# vera-module.net
KiCad netlist of a schematic drawn in EAGLE
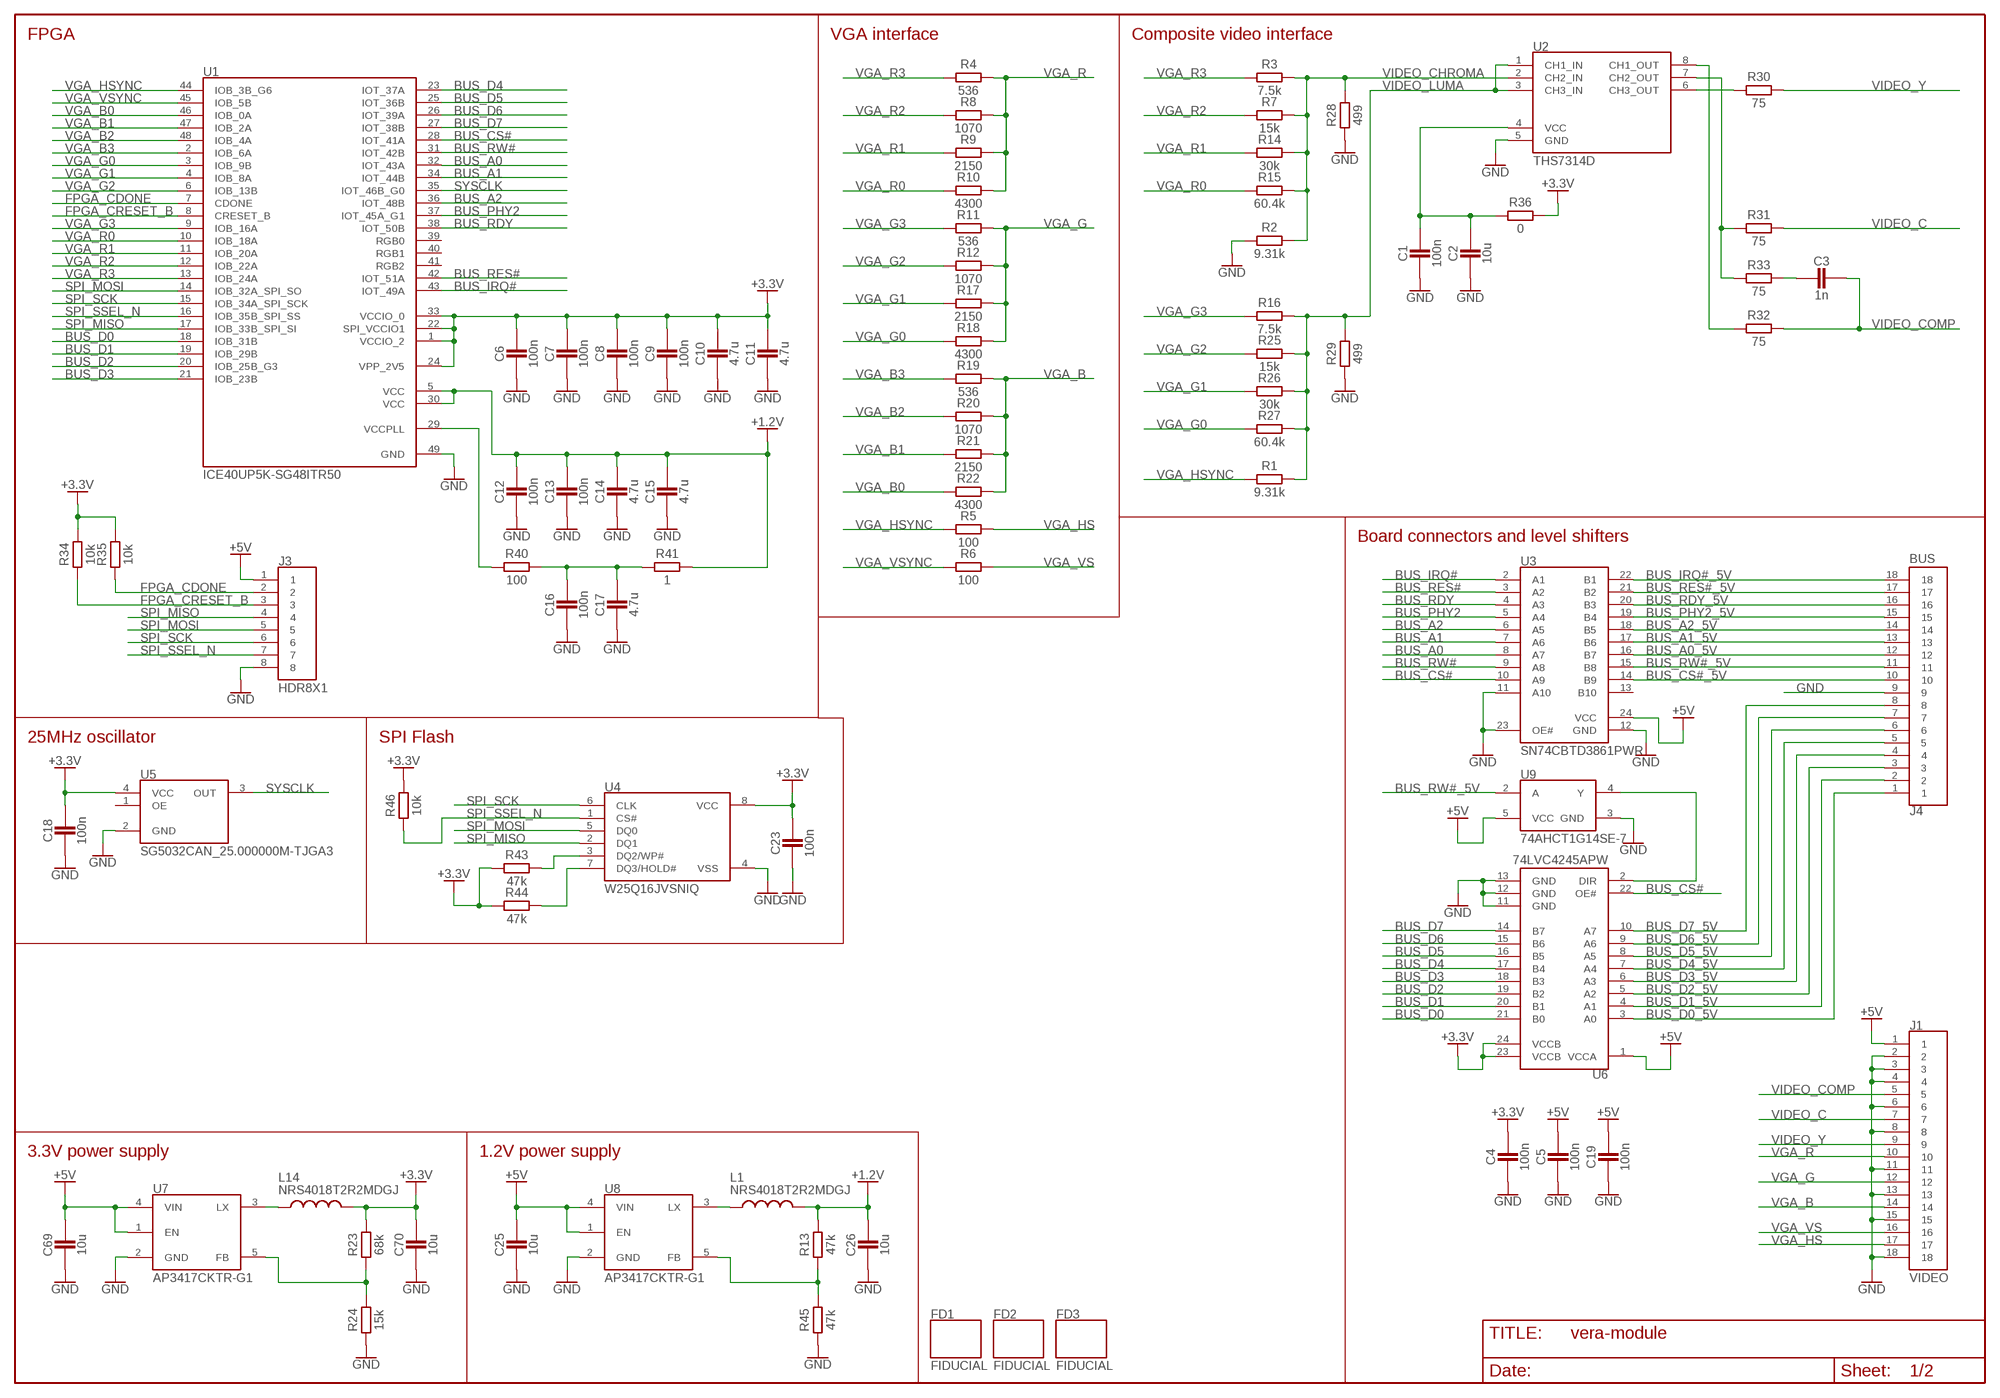
[diagram p0: schematic, sheet 1]
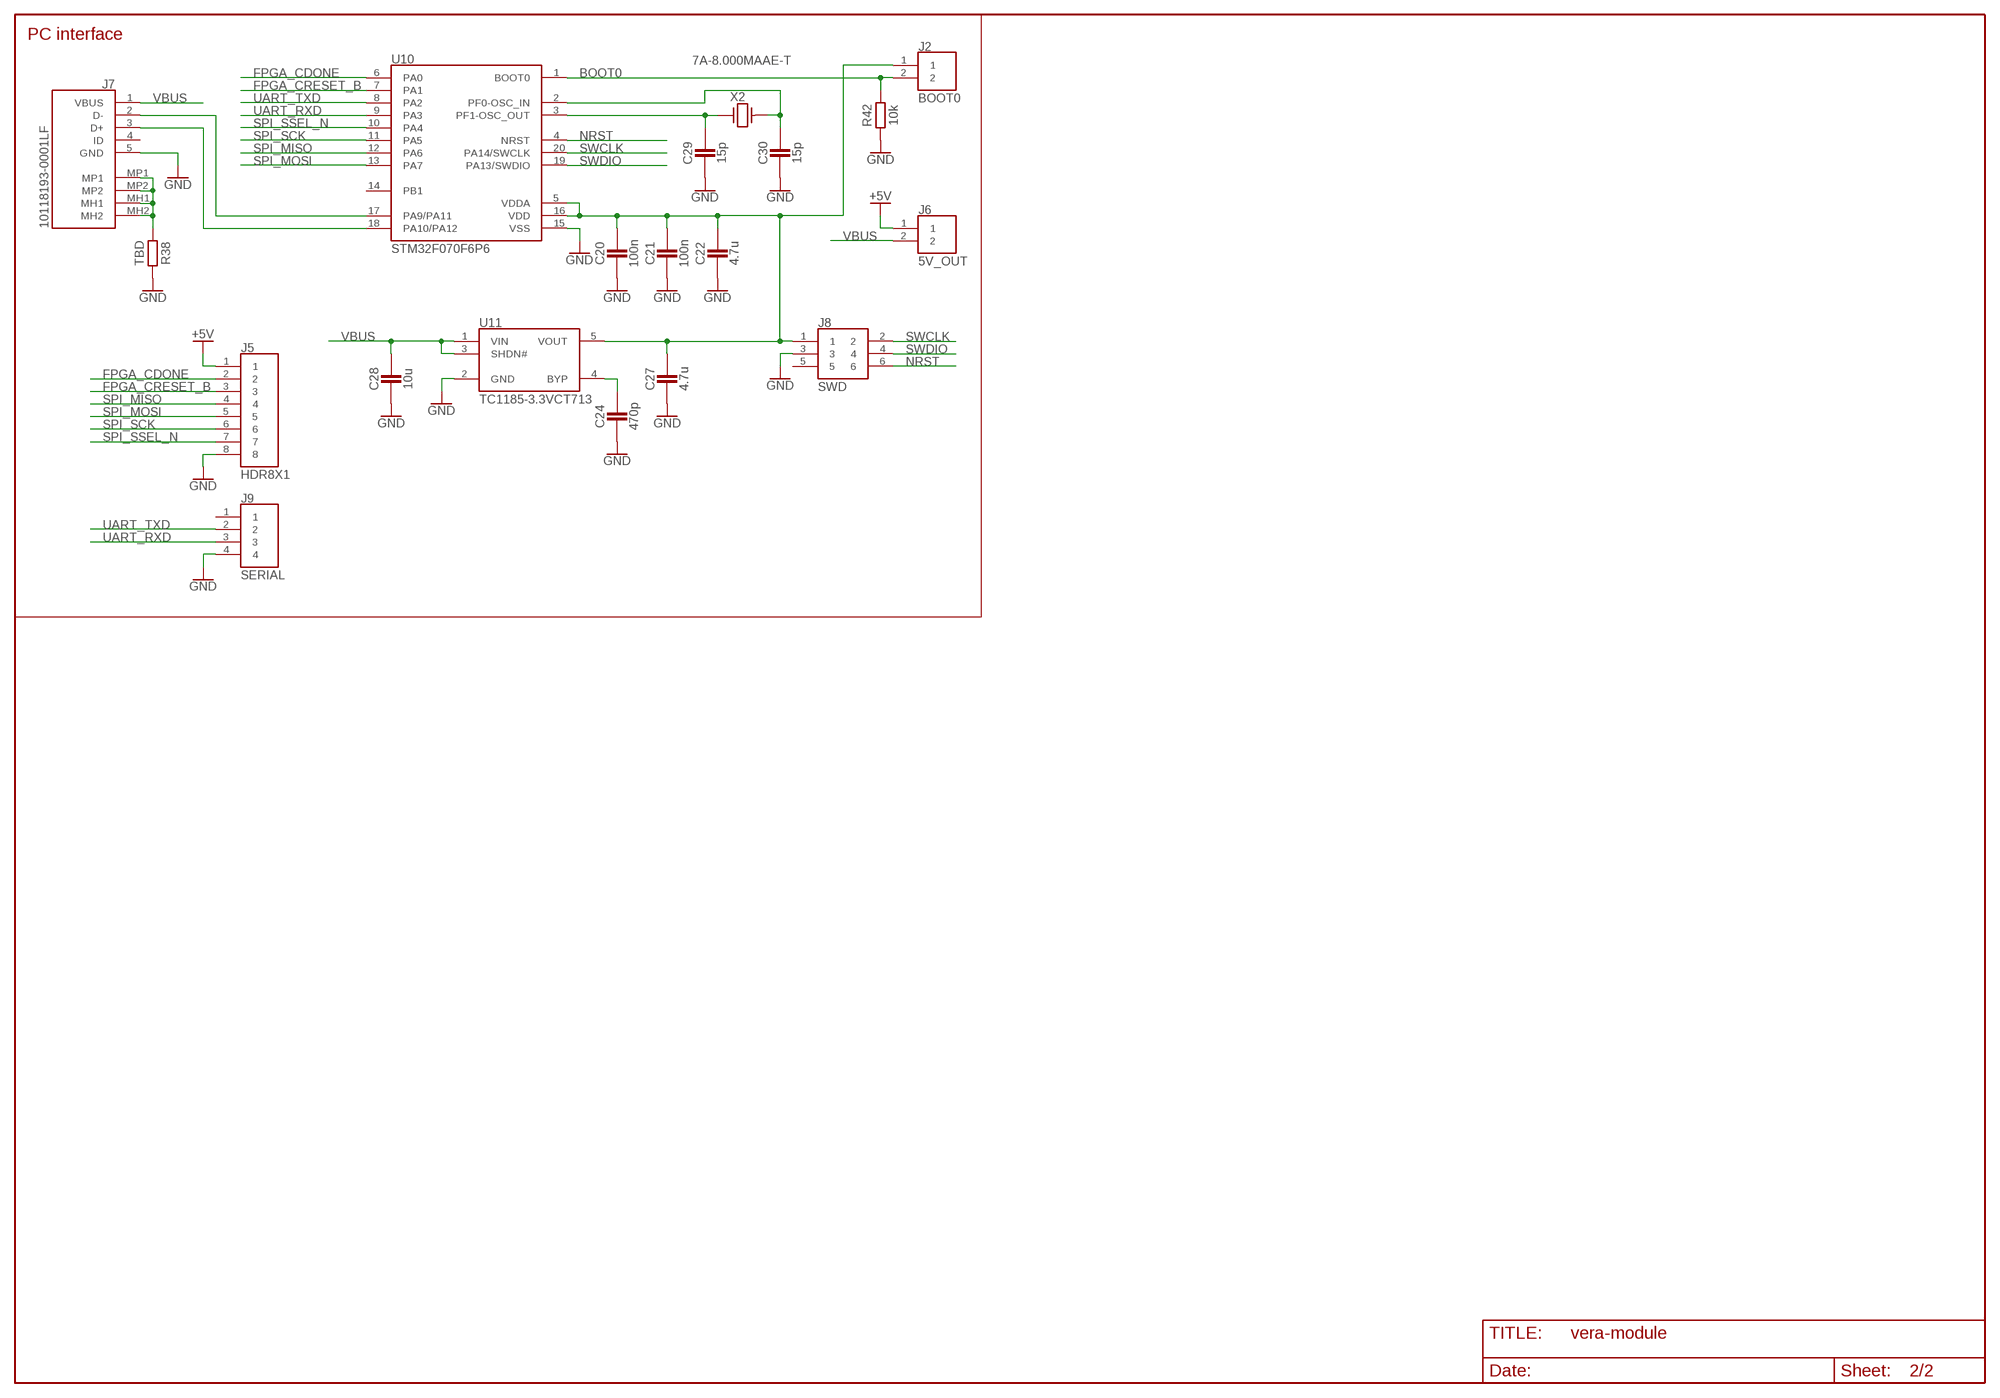
[diagram p1: schematic, sheet 2]

(export (version "E")
  (design (tool "Eeschema 10.0.6"))
  (components
    (comp (ref "C1")
      (value "100n")
      (footprint "eagle-import:C0603")
      (libsource (lib "eagle-import") (part "CAPACITOR0603"))
    )
    (comp (ref "C2")
      (value "10u")
      (footprint "eagle-import:C0805")
      (libsource (lib "eagle-import") (part "CAPACITOR0805"))
    )
    (comp (ref "C3")
      (value "1n")
      (footprint "eagle-import:C0603")
      (libsource (lib "eagle-import") (part "CAPACITOR0603"))
    )
    (comp (ref "C4")
      (value "100n")
      (footprint "eagle-import:C0603")
      (libsource (lib "eagle-import") (part "CAPACITOR0603"))
    )
    (comp (ref "C5")
      (value "100n")
      (footprint "eagle-import:C0603")
      (libsource (lib "eagle-import") (part "CAPACITOR0603"))
    )
    (comp (ref "C6")
      (value "100n")
      (footprint "eagle-import:C0603")
      (libsource (lib "eagle-import") (part "CAPACITOR0603"))
    )
    (comp (ref "C7")
      (value "100n")
      (footprint "eagle-import:C0603")
      (libsource (lib "eagle-import") (part "CAPACITOR0603"))
    )
    (comp (ref "C8")
      (value "100n")
      (footprint "eagle-import:C0603")
      (libsource (lib "eagle-import") (part "CAPACITOR0603"))
    )
    (comp (ref "C9")
      (value "100n")
      (footprint "eagle-import:C0603")
      (libsource (lib "eagle-import") (part "CAPACITOR0603"))
    )
    (comp (ref "C10")
      (value "4.7u")
      (footprint "eagle-import:C0603")
      (libsource (lib "eagle-import") (part "CAPACITOR0603"))
    )
    (comp (ref "C11")
      (value "4.7u")
      (footprint "eagle-import:C0603")
      (libsource (lib "eagle-import") (part "CAPACITOR0603"))
    )
    (comp (ref "C12")
      (value "100n")
      (footprint "eagle-import:C0603")
      (libsource (lib "eagle-import") (part "CAPACITOR0603"))
    )
    (comp (ref "C13")
      (value "100n")
      (footprint "eagle-import:C0603")
      (libsource (lib "eagle-import") (part "CAPACITOR0603"))
    )
    (comp (ref "C14")
      (value "4.7u")
      (footprint "eagle-import:C0603")
      (libsource (lib "eagle-import") (part "CAPACITOR0603"))
    )
    (comp (ref "C15")
      (value "4.7u")
      (footprint "eagle-import:C0603")
      (libsource (lib "eagle-import") (part "CAPACITOR0603"))
    )
    (comp (ref "C16")
      (value "100n")
      (footprint "eagle-import:C0603")
      (libsource (lib "eagle-import") (part "CAPACITOR0603"))
    )
    (comp (ref "C17")
      (value "4.7u")
      (footprint "eagle-import:C0603")
      (libsource (lib "eagle-import") (part "CAPACITOR0603"))
    )
    (comp (ref "C18")
      (value "100n")
      (footprint "eagle-import:C0603")
      (libsource (lib "eagle-import") (part "CAPACITOR0603"))
    )
    (comp (ref "C19")
      (value "100n")
      (footprint "eagle-import:C0603")
      (libsource (lib "eagle-import") (part "CAPACITOR0603"))
    )
    (comp (ref "C23")
      (value "100n")
      (footprint "eagle-import:C0603")
      (libsource (lib "eagle-import") (part "CAPACITOR0603"))
    )
    (comp (ref "C25")
      (value "10u")
      (footprint "eagle-import:C0805")
      (libsource (lib "eagle-import") (part "CAPACITOR0805"))
    )
    (comp (ref "C26")
      (value "10u")
      (footprint "eagle-import:C0805")
      (libsource (lib "eagle-import") (part "CAPACITOR0805"))
    )
    (comp (ref "C69")
      (value "10u")
      (footprint "eagle-import:C0805")
      (libsource (lib "eagle-import") (part "CAPACITOR0805"))
    )
    (comp (ref "C70")
      (value "10u")
      (footprint "eagle-import:C0805")
      (libsource (lib "eagle-import") (part "CAPACITOR0805"))
    )
    (comp (ref "FD1")
      (value "FIDUCIAL")
      (footprint "eagle-import:FIDUCIAL")
      (libsource (lib "eagle-import") (part "FIDUCIAL"))
    )
    (comp (ref "FD2")
      (value "FIDUCIAL")
      (footprint "eagle-import:FIDUCIAL")
      (libsource (lib "eagle-import") (part "FIDUCIAL"))
    )
    (comp (ref "FD3")
      (value "FIDUCIAL")
      (footprint "eagle-import:FIDUCIAL")
      (libsource (lib "eagle-import") (part "FIDUCIAL"))
    )
    (comp (ref "J1")
      (value "VIDEO")
      (footprint "eagle-import:HDR18X1")
      (libsource (lib "eagle-import") (part "HDR18X1"))
    )
    (comp (ref "J3")
      (value "HDR8X1")
      (footprint "eagle-import:HDR8X1")
      (libsource (lib "eagle-import") (part "HDR8X1"))
    )
    (comp (ref "J4")
      (value "BUS")
      (footprint "eagle-import:HDR18X1")
      (libsource (lib "eagle-import") (part "HDR18X1"))
    )
    (comp (ref "L1")
      (value "NRS4018T2R2MDGJ")
      (footprint "eagle-import:NRS4018")
      (libsource (lib "eagle-import") (part "INDUCTORNRS4018"))
    )
    (comp (ref "L14")
      (value "NRS4018T2R2MDGJ")
      (footprint "eagle-import:NRS4018")
      (libsource (lib "eagle-import") (part "INDUCTORNRS4018"))
    )
    (comp (ref "R1")
      (value "9.31k")
      (footprint "eagle-import:R0603")
      (libsource (lib "eagle-import") (part "RESISTOR0603"))
    )
    (comp (ref "R2")
      (value "9.31k")
      (footprint "eagle-import:R0603")
      (libsource (lib "eagle-import") (part "RESISTOR0603"))
    )
    (comp (ref "R3")
      (value "7.5k")
      (footprint "eagle-import:R0603")
      (libsource (lib "eagle-import") (part "RESISTOR0603"))
    )
    (comp (ref "R4")
      (value "536")
      (footprint "eagle-import:R0603")
      (libsource (lib "eagle-import") (part "RESISTOR0603"))
    )
    (comp (ref "R5")
      (value "100")
      (footprint "eagle-import:R0603")
      (libsource (lib "eagle-import") (part "RESISTOR0603"))
    )
    (comp (ref "R6")
      (value "100")
      (footprint "eagle-import:R0603")
      (libsource (lib "eagle-import") (part "RESISTOR0603"))
    )
    (comp (ref "R7")
      (value "15k")
      (footprint "eagle-import:R0603")
      (libsource (lib "eagle-import") (part "RESISTOR0603"))
    )
    (comp (ref "R8")
      (value "1070")
      (footprint "eagle-import:R0603")
      (libsource (lib "eagle-import") (part "RESISTOR0603"))
    )
    (comp (ref "R9")
      (value "2150")
      (footprint "eagle-import:R0603")
      (libsource (lib "eagle-import") (part "RESISTOR0603"))
    )
    (comp (ref "R10")
      (value "4300")
      (footprint "eagle-import:R0603")
      (libsource (lib "eagle-import") (part "RESISTOR0603"))
    )
    (comp (ref "R11")
      (value "536")
      (footprint "eagle-import:R0603")
      (libsource (lib "eagle-import") (part "RESISTOR0603"))
    )
    (comp (ref "R12")
      (value "1070")
      (footprint "eagle-import:R0603")
      (libsource (lib "eagle-import") (part "RESISTOR0603"))
    )
    (comp (ref "R13")
      (value "47k")
      (footprint "eagle-import:R0603")
      (libsource (lib "eagle-import") (part "RESISTOR0603"))
    )
    (comp (ref "R14")
      (value "30k")
      (footprint "eagle-import:R0603")
      (libsource (lib "eagle-import") (part "RESISTOR0603"))
    )
    (comp (ref "R15")
      (value "60.4k")
      (footprint "eagle-import:R0603")
      (libsource (lib "eagle-import") (part "RESISTOR0603"))
    )
    (comp (ref "R16")
      (value "7.5k")
      (footprint "eagle-import:R0603")
      (libsource (lib "eagle-import") (part "RESISTOR0603"))
    )
    (comp (ref "R17")
      (value "2150")
      (footprint "eagle-import:R0603")
      (libsource (lib "eagle-import") (part "RESISTOR0603"))
    )
    (comp (ref "R18")
      (value "4300")
      (footprint "eagle-import:R0603")
      (libsource (lib "eagle-import") (part "RESISTOR0603"))
    )
    (comp (ref "R19")
      (value "536")
      (footprint "eagle-import:R0603")
      (libsource (lib "eagle-import") (part "RESISTOR0603"))
    )
    (comp (ref "R20")
      (value "1070")
      (footprint "eagle-import:R0603")
      (libsource (lib "eagle-import") (part "RESISTOR0603"))
    )
    (comp (ref "R21")
      (value "2150")
      (footprint "eagle-import:R0603")
      (libsource (lib "eagle-import") (part "RESISTOR0603"))
    )
    (comp (ref "R22")
      (value "4300")
      (footprint "eagle-import:R0603")
      (libsource (lib "eagle-import") (part "RESISTOR0603"))
    )
    (comp (ref "R23")
      (value "68k")
      (footprint "eagle-import:R0603")
      (libsource (lib "eagle-import") (part "RESISTOR0603"))
    )
    (comp (ref "R24")
      (value "15k")
      (footprint "eagle-import:R0603")
      (libsource (lib "eagle-import") (part "RESISTOR0603"))
    )
    (comp (ref "R25")
      (value "15k")
      (footprint "eagle-import:R0603")
      (libsource (lib "eagle-import") (part "RESISTOR0603"))
    )
    (comp (ref "R26")
      (value "30k")
      (footprint "eagle-import:R0603")
      (libsource (lib "eagle-import") (part "RESISTOR0603"))
    )
    (comp (ref "R27")
      (value "60.4k")
      (footprint "eagle-import:R0603")
      (libsource (lib "eagle-import") (part "RESISTOR0603"))
    )
    (comp (ref "R28")
      (value "499")
      (footprint "eagle-import:R0603")
      (libsource (lib "eagle-import") (part "RESISTOR0603"))
    )
    (comp (ref "R29")
      (value "499")
      (footprint "eagle-import:R0603")
      (libsource (lib "eagle-import") (part "RESISTOR0603"))
    )
    (comp (ref "R30")
      (value "75")
      (footprint "eagle-import:R0603")
      (libsource (lib "eagle-import") (part "RESISTOR0603"))
    )
    (comp (ref "R31")
      (value "75")
      (footprint "eagle-import:R0603")
      (libsource (lib "eagle-import") (part "RESISTOR0603"))
    )
    (comp (ref "R32")
      (value "75")
      (footprint "eagle-import:R0603")
      (libsource (lib "eagle-import") (part "RESISTOR0603"))
    )
    (comp (ref "R33")
      (value "75")
      (footprint "eagle-import:R0603")
      (libsource (lib "eagle-import") (part "RESISTOR0603"))
    )
    (comp (ref "R34")
      (value "10k")
      (footprint "eagle-import:R0603")
      (libsource (lib "eagle-import") (part "RESISTOR0603"))
    )
    (comp (ref "R35")
      (value "10k")
      (footprint "eagle-import:R0603")
      (libsource (lib "eagle-import") (part "RESISTOR0603"))
    )
    (comp (ref "R36")
      (value "0")
      (footprint "eagle-import:R0603")
      (libsource (lib "eagle-import") (part "RESISTOR0603"))
    )
    (comp (ref "R40")
      (value "100")
      (footprint "eagle-import:R0603")
      (libsource (lib "eagle-import") (part "RESISTOR0603"))
    )
    (comp (ref "R41")
      (value "1")
      (footprint "eagle-import:R0603")
      (libsource (lib "eagle-import") (part "RESISTOR0603"))
    )
    (comp (ref "R43")
      (value "47k")
      (footprint "eagle-import:R0603")
      (libsource (lib "eagle-import") (part "RESISTOR0603"))
    )
    (comp (ref "R44")
      (value "47k")
      (footprint "eagle-import:R0603")
      (libsource (lib "eagle-import") (part "RESISTOR0603"))
    )
    (comp (ref "R45")
      (value "47k")
      (footprint "eagle-import:R0603")
      (libsource (lib "eagle-import") (part "RESISTOR0603"))
    )
    (comp (ref "R46")
      (value "10k")
      (footprint "eagle-import:R0603")
      (libsource (lib "eagle-import") (part "RESISTOR0603"))
    )
    (comp (ref "U1")
      (value "ICE40UP5K-SG48ITR50")
      (footprint "eagle-import:QFN-48")
      (libsource (lib "eagle-import") (part "ICE40UP5K-SG48ITR50"))
    )
    (comp (ref "U2")
      (value "THS7314D")
      (footprint "eagle-import:SOIC-8")
      (libsource (lib "eagle-import") (part "THS7314D"))
    )
    (comp (ref "U3")
      (value "SN74CBTD3861PWR")
      (footprint "eagle-import:TSSOP-24")
      (libsource (lib "eagle-import") (part "SN74CBTD3861PWR"))
    )
    (comp (ref "U4")
      (value "W25Q16JVSNIQ")
      (footprint "eagle-import:SOIC-8")
      (libsource (lib "eagle-import") (part "QSPI_FLASHSOIC8"))
    )
    (comp (ref "U5")
      (value "SG5032CAN_25.000000M-TJGA3")
      (footprint "eagle-import:SG5032")
      (libsource (lib "eagle-import") (part "SG5032CAN_40.000000M-TJGA3"))
    )
    (comp (ref "U6")
      (value "74LVC4245APW")
      (footprint "eagle-import:TSSOP-24")
      (libsource (lib "eagle-import") (part "74LVC4245APW"))
    )
    (comp (ref "U7")
      (value "AP3417CKTR-G1")
      (footprint "eagle-import:SOT-23-5")
      (libsource (lib "eagle-import") (part "AP3417CKTR-G1"))
    )
    (comp (ref "U8")
      (value "AP3417CKTR-G1")
      (footprint "eagle-import:SOT-23-5")
      (libsource (lib "eagle-import") (part "AP3417CKTR-G1"))
    )
    (comp (ref "U9")
      (value "74AHCT1G14SE-7")
      (footprint "eagle-import:TSSOP-5")
      (libsource (lib "eagle-import") (part "74AHCT1G14SE-7"))
    )
    (comp (ref "C20")
      (value "100n")
      (footprint "eagle-import:C0603")
      (libsource (lib "eagle-import") (part "CAPACITOR0603"))
    )
    (comp (ref "C21")
      (value "100n")
      (footprint "eagle-import:C0603")
      (libsource (lib "eagle-import") (part "CAPACITOR0603"))
    )
    (comp (ref "C22")
      (value "4.7u")
      (footprint "eagle-import:C0603")
      (libsource (lib "eagle-import") (part "CAPACITOR0603"))
    )
    (comp (ref "C24")
      (value "470p")
      (footprint "eagle-import:C0603")
      (libsource (lib "eagle-import") (part "CAPACITOR0603"))
    )
    (comp (ref "C27")
      (value "4.7u")
      (footprint "eagle-import:C0603")
      (libsource (lib "eagle-import") (part "CAPACITOR0603"))
    )
    (comp (ref "C28")
      (value "10u")
      (footprint "eagle-import:C0805")
      (libsource (lib "eagle-import") (part "CAPACITOR0805"))
    )
    (comp (ref "C29")
      (value "15p")
      (footprint "eagle-import:C0603")
      (libsource (lib "eagle-import") (part "CAPACITOR0603"))
    )
    (comp (ref "C30")
      (value "15p")
      (footprint "eagle-import:C0603")
      (libsource (lib "eagle-import") (part "CAPACITOR0603"))
    )
    (comp (ref "J2")
      (value "BOOT0")
      (footprint "eagle-import:HDR2X1")
      (libsource (lib "eagle-import") (part "HDR2X1"))
    )
    (comp (ref "J5")
      (value "HDR8X1")
      (footprint "eagle-import:HDR8X1")
      (libsource (lib "eagle-import") (part "HDR8X1"))
    )
    (comp (ref "J6")
      (value "5V_OUT")
      (footprint "eagle-import:HDR2X1")
      (libsource (lib "eagle-import") (part "HDR2X1"))
    )
    (comp (ref "J7")
      (value "10118193-0001LF")
      (footprint "eagle-import:10118193-0001LF")
      (libsource (lib "eagle-import") (part "10118193-0001LF"))
    )
    (comp (ref "J8")
      (value "SWD")
      (footprint "eagle-import:HDR2X3")
      (libsource (lib "eagle-import") (part "HDR2X3"))
    )
    (comp (ref "J9")
      (value "SERIAL")
      (footprint "eagle-import:HDR4X1")
      (libsource (lib "eagle-import") (part "HDR4X1"))
    )
    (comp (ref "R38")
      (value "TBD")
      (footprint "eagle-import:R0603")
      (libsource (lib "eagle-import") (part "RESISTOR0603"))
    )
    (comp (ref "R42")
      (value "10k")
      (footprint "eagle-import:R0603")
      (libsource (lib "eagle-import") (part "RESISTOR0603"))
    )
    (comp (ref "U10")
      (value "STM32F070F6P6")
      (footprint "eagle-import:TSSOP-20")
      (libsource (lib "eagle-import") (part "STM32F070F6P6"))
    )
    (comp (ref "U11")
      (value "TC1185-3.3VCT713")
      (footprint "eagle-import:SOT-23-5")
      (libsource (lib "eagle-import") (part "TC1185-3.3VCT713"))
    )
    (comp (ref "X2")
      (value "7A-8.000MAAE-T")
      (footprint "eagle-import:XTAL2_5X3.2")
      (libsource (lib "eagle-import") (part "XTAL2_5X3.2"))
    )
  )
  (nets
    (net (code "1") (name "+1.2V") (class "Default")
      (node (ref "C12") (pin "2") (pinfunction "2_2") (pintype "passive"))
      (node (ref "C13") (pin "2") (pinfunction "2_2") (pintype "passive"))
      (node (ref "C14") (pin "2") (pinfunction "2_2") (pintype "passive"))
      (node (ref "C15") (pin "2") (pinfunction "2_2") (pintype "passive"))
      (node (ref "C26") (pin "2") (pinfunction "2_2") (pintype "passive"))
      (node (ref "L1") (pin "2") (pinfunction "2_2") (pintype "passive"))
      (node (ref "R13") (pin "2") (pinfunction "2_2") (pintype "passive"))
      (node (ref "R41") (pin "2") (pinfunction "2_2") (pintype "passive"))
      (node (ref "U1") (pin "30") (pinfunction "VCC_30") (pintype "passive"))
      (node (ref "U1") (pin "5") (pinfunction "VCC_5") (pintype "passive"))
    )
    (net (code "2") (name "+3.3V") (class "Default")
      (node (ref "C10") (pin "2") (pinfunction "2_2") (pintype "passive"))
      (node (ref "C11") (pin "2") (pinfunction "2_2") (pintype "passive"))
      (node (ref "C18") (pin "2") (pinfunction "2_2") (pintype "passive"))
      (node (ref "C23") (pin "2") (pinfunction "2_2") (pintype "passive"))
      (node (ref "C4") (pin "2") (pinfunction "2_2") (pintype "passive"))
      (node (ref "C6") (pin "2") (pinfunction "2_2") (pintype "passive"))
      (node (ref "C7") (pin "2") (pinfunction "2_2") (pintype "passive"))
      (node (ref "C70") (pin "2") (pinfunction "2_2") (pintype "passive"))
      (node (ref "C8") (pin "2") (pinfunction "2_2") (pintype "passive"))
      (node (ref "C9") (pin "2") (pinfunction "2_2") (pintype "passive"))
      (node (ref "L14") (pin "2") (pinfunction "2_2") (pintype "passive"))
      (node (ref "R23") (pin "2") (pinfunction "2_2") (pintype "passive"))
      (node (ref "R34") (pin "1") (pinfunction "1_1") (pintype "passive"))
      (node (ref "R35") (pin "1") (pinfunction "1_1") (pintype "passive"))
      (node (ref "R36") (pin "2") (pinfunction "2_2") (pintype "passive"))
      (node (ref "R43") (pin "1") (pinfunction "1_1") (pintype "passive"))
      (node (ref "R44") (pin "1") (pinfunction "1_1") (pintype "passive"))
      (node (ref "R46") (pin "1") (pinfunction "1_1") (pintype "passive"))
      (node (ref "U1") (pin "1") (pinfunction "VCCIO_2_1") (pintype "passive"))
      (node (ref "U1") (pin "22") (pinfunction "SPI_VCCIO1_22") (pintype "passive"))
      (node (ref "U1") (pin "24") (pinfunction "VPP_2V5_24") (pintype "passive"))
      (node (ref "U1") (pin "33") (pinfunction "VCCIO_0_33") (pintype "passive"))
      (node (ref "U4") (pin "8") (pinfunction "VCC_8") (pintype "passive"))
      (node (ref "U5") (pin "4") (pinfunction "VCC_4") (pintype "passive"))
      (node (ref "U6") (pin "23") (pinfunction "VCCB_23") (pintype "passive"))
      (node (ref "U6") (pin "24") (pinfunction "VCCB_24") (pintype "passive"))
    )
    (net (code "3") (name "+5V") (class "Default")
      (node (ref "C19") (pin "2") (pinfunction "2_2") (pintype "passive"))
      (node (ref "C25") (pin "2") (pinfunction "2_2") (pintype "passive"))
      (node (ref "C5") (pin "2") (pinfunction "2_2") (pintype "passive"))
      (node (ref "C69") (pin "2") (pinfunction "2_2") (pintype "passive"))
      (node (ref "J1") (pin "1") (pinfunction "1_1") (pintype "passive"))
      (node (ref "J3") (pin "1") (pinfunction "1_1") (pintype "passive"))
      (node (ref "J5") (pin "1") (pinfunction "1_1") (pintype "passive"))
      (node (ref "J6") (pin "1") (pinfunction "1_1") (pintype "passive"))
      (node (ref "U3") (pin "24") (pinfunction "VCC_24") (pintype "passive"))
      (node (ref "U6") (pin "1") (pinfunction "VCCA_1") (pintype "passive"))
      (node (ref "U7") (pin "1") (pinfunction "EN_1") (pintype "passive"))
      (node (ref "U7") (pin "4") (pinfunction "VIN_4") (pintype "passive"))
      (node (ref "U8") (pin "1") (pinfunction "EN_1") (pintype "passive"))
      (node (ref "U8") (pin "4") (pinfunction "VIN_4") (pintype "passive"))
      (node (ref "U9") (pin "5") (pinfunction "VCC_5") (pintype "passive"))
    )
    (net (code "4") (name "BOOT0") (class "Default")
      (node (ref "J2") (pin "2") (pinfunction "2_2") (pintype "passive"))
      (node (ref "R42") (pin "2") (pinfunction "2_2") (pintype "passive"))
      (node (ref "U10") (pin "1") (pinfunction "BOOT0_1") (pintype "passive"))
    )
    (net (code "5") (name "BUS_A0") (class "Default")
      (node (ref "U1") (pin "32") (pinfunction "IOT_43A_32") (pintype "passive"))
      (node (ref "U3") (pin "8") (pinfunction "A7_8") (pintype "passive"))
    )
    (net (code "6") (name "BUS_A0_5V") (class "Default")
      (node (ref "J4") (pin "12") (pinfunction "12_12") (pintype "passive"))
      (node (ref "U3") (pin "16") (pinfunction "B7_16") (pintype "passive"))
    )
    (net (code "7") (name "BUS_A1") (class "Default")
      (node (ref "U1") (pin "34") (pinfunction "IOT_44B_34") (pintype "passive"))
      (node (ref "U3") (pin "7") (pinfunction "A6_7") (pintype "passive"))
    )
    (net (code "8") (name "BUS_A1_5V") (class "Default")
      (node (ref "J4") (pin "13") (pinfunction "13_13") (pintype "passive"))
      (node (ref "U3") (pin "17") (pinfunction "B6_17") (pintype "passive"))
    )
    (net (code "9") (name "BUS_A2") (class "Default")
      (node (ref "U1") (pin "36") (pinfunction "IOT_48B_36") (pintype "passive"))
      (node (ref "U3") (pin "6") (pinfunction "A5_6") (pintype "passive"))
    )
    (net (code "10") (name "BUS_A2_5V") (class "Default")
      (node (ref "J4") (pin "14") (pinfunction "14_14") (pintype "passive"))
      (node (ref "U3") (pin "18") (pinfunction "B5_18") (pintype "passive"))
    )
    (net (code "11") (name "BUS_CS#") (class "Default")
      (node (ref "U1") (pin "28") (pinfunction "IOT_41A_28") (pintype "passive"))
      (node (ref "U3") (pin "10") (pinfunction "A9_10") (pintype "passive"))
      (node (ref "U6") (pin "22") (pinfunction "OE#_22") (pintype "passive"))
    )
    (net (code "12") (name "BUS_CS#_5V") (class "Default")
      (node (ref "J4") (pin "10") (pinfunction "10_10") (pintype "passive"))
      (node (ref "U3") (pin "14") (pinfunction "B9_14") (pintype "passive"))
    )
    (net (code "13") (name "BUS_D0") (class "Default")
      (node (ref "U1") (pin "18") (pinfunction "IOB_31B_18") (pintype "passive"))
      (node (ref "U6") (pin "21") (pinfunction "B0_21") (pintype "passive"))
    )
    (net (code "14") (name "BUS_D0_5V") (class "Default")
      (node (ref "J4") (pin "1") (pinfunction "1_1") (pintype "passive"))
      (node (ref "U6") (pin "3") (pinfunction "A0_3") (pintype "passive"))
    )
    (net (code "15") (name "BUS_D1") (class "Default")
      (node (ref "U1") (pin "19") (pinfunction "IOB_29B_19") (pintype "passive"))
      (node (ref "U6") (pin "20") (pinfunction "B1_20") (pintype "passive"))
    )
    (net (code "16") (name "BUS_D1_5V") (class "Default")
      (node (ref "J4") (pin "2") (pinfunction "2_2") (pintype "passive"))
      (node (ref "U6") (pin "4") (pinfunction "A1_4") (pintype "passive"))
    )
    (net (code "17") (name "BUS_D2") (class "Default")
      (node (ref "U1") (pin "20") (pinfunction "IOB_25B_G3_20") (pintype "passive"))
      (node (ref "U6") (pin "19") (pinfunction "B2_19") (pintype "passive"))
    )
    (net (code "18") (name "BUS_D2_5V") (class "Default")
      (node (ref "J4") (pin "3") (pinfunction "3_3") (pintype "passive"))
      (node (ref "U6") (pin "5") (pinfunction "A2_5") (pintype "passive"))
    )
    (net (code "19") (name "BUS_D3") (class "Default")
      (node (ref "U1") (pin "21") (pinfunction "IOB_23B_21") (pintype "passive"))
      (node (ref "U6") (pin "18") (pinfunction "B3_18") (pintype "passive"))
    )
    (net (code "20") (name "BUS_D3_5V") (class "Default")
      (node (ref "J4") (pin "4") (pinfunction "4_4") (pintype "passive"))
      (node (ref "U6") (pin "6") (pinfunction "A3_6") (pintype "passive"))
    )
    (net (code "21") (name "BUS_D4") (class "Default")
      (node (ref "U1") (pin "23") (pinfunction "IOT_37A_23") (pintype "passive"))
      (node (ref "U6") (pin "17") (pinfunction "B4_17") (pintype "passive"))
    )
    (net (code "22") (name "BUS_D4_5V") (class "Default")
      (node (ref "J4") (pin "5") (pinfunction "5_5") (pintype "passive"))
      (node (ref "U6") (pin "7") (pinfunction "A4_7") (pintype "passive"))
    )
    (net (code "23") (name "BUS_D5") (class "Default")
      (node (ref "U1") (pin "25") (pinfunction "IOT_36B_25") (pintype "passive"))
      (node (ref "U6") (pin "16") (pinfunction "B5_16") (pintype "passive"))
    )
    (net (code "24") (name "BUS_D5_5V") (class "Default")
      (node (ref "J4") (pin "6") (pinfunction "6_6") (pintype "passive"))
      (node (ref "U6") (pin "8") (pinfunction "A5_8") (pintype "passive"))
    )
    (net (code "25") (name "BUS_D6") (class "Default")
      (node (ref "U1") (pin "26") (pinfunction "IOT_39A_26") (pintype "passive"))
      (node (ref "U6") (pin "15") (pinfunction "B6_15") (pintype "passive"))
    )
    (net (code "26") (name "BUS_D6_5V") (class "Default")
      (node (ref "J4") (pin "7") (pinfunction "7_7") (pintype "passive"))
      (node (ref "U6") (pin "9") (pinfunction "A6_9") (pintype "passive"))
    )
    (net (code "27") (name "BUS_D7") (class "Default")
      (node (ref "U1") (pin "27") (pinfunction "IOT_38B_27") (pintype "passive"))
      (node (ref "U6") (pin "14") (pinfunction "B7_14") (pintype "passive"))
    )
    (net (code "28") (name "BUS_D7_5V") (class "Default")
      (node (ref "J4") (pin "8") (pinfunction "8_8") (pintype "passive"))
      (node (ref "U6") (pin "10") (pinfunction "A7_10") (pintype "passive"))
    )
    (net (code "29") (name "BUS_IRQ#") (class "Default")
      (node (ref "U1") (pin "43") (pinfunction "IOT_49A_43") (pintype "passive"))
      (node (ref "U3") (pin "2") (pinfunction "A1_2") (pintype "passive"))
    )
    (net (code "30") (name "BUS_IRQ#_5V") (class "Default")
      (node (ref "J4") (pin "18") (pinfunction "18_18") (pintype "passive"))
      (node (ref "U3") (pin "22") (pinfunction "B1_22") (pintype "passive"))
    )
    (net (code "31") (name "BUS_PHY2") (class "Default")
      (node (ref "U1") (pin "37") (pinfunction "IOT_45A_G1_37") (pintype "passive"))
      (node (ref "U3") (pin "5") (pinfunction "A4_5") (pintype "passive"))
    )
    (net (code "32") (name "BUS_PHY2_5V") (class "Default")
      (node (ref "J4") (pin "15") (pinfunction "15_15") (pintype "passive"))
      (node (ref "U3") (pin "19") (pinfunction "B4_19") (pintype "passive"))
    )
    (net (code "33") (name "BUS_RDY") (class "Default")
      (node (ref "U1") (pin "38") (pinfunction "IOT_50B_38") (pintype "passive"))
      (node (ref "U3") (pin "4") (pinfunction "A3_4") (pintype "passive"))
    )
    (net (code "34") (name "BUS_RDY_5V") (class "Default")
      (node (ref "J4") (pin "16") (pinfunction "16_16") (pintype "passive"))
      (node (ref "U3") (pin "20") (pinfunction "B3_20") (pintype "passive"))
    )
    (net (code "35") (name "BUS_RES#") (class "Default")
      (node (ref "U1") (pin "42") (pinfunction "IOT_51A_42") (pintype "passive"))
      (node (ref "U3") (pin "3") (pinfunction "A2_3") (pintype "passive"))
    )
    (net (code "36") (name "BUS_RES#_5V") (class "Default")
      (node (ref "J4") (pin "17") (pinfunction "17_17") (pintype "passive"))
      (node (ref "U3") (pin "21") (pinfunction "B2_21") (pintype "passive"))
    )
    (net (code "37") (name "BUS_RW#") (class "Default")
      (node (ref "U1") (pin "31") (pinfunction "IOT_42B_31") (pintype "passive"))
      (node (ref "U3") (pin "9") (pinfunction "A8_9") (pintype "passive"))
    )
    (net (code "38") (name "BUS_RW#_5V") (class "Default")
      (node (ref "J4") (pin "11") (pinfunction "11_11") (pintype "passive"))
      (node (ref "U3") (pin "15") (pinfunction "B8_15") (pintype "passive"))
      (node (ref "U9") (pin "2") (pinfunction "A_2") (pintype "passive"))
    )
    (net (code "39") (name "FPGA_CDONE") (class "Default")
      (node (ref "J3") (pin "2") (pinfunction "2_2") (pintype "passive"))
      (node (ref "J5") (pin "2") (pinfunction "2_2") (pintype "passive"))
      (node (ref "R35") (pin "2") (pinfunction "2_2") (pintype "passive"))
      (node (ref "U1") (pin "7") (pinfunction "CDONE_7") (pintype "passive"))
      (node (ref "U10") (pin "6") (pinfunction "PA0_6") (pintype "passive"))
    )
    (net (code "40") (name "FPGA_CRESET_B") (class "Default")
      (node (ref "J3") (pin "3") (pinfunction "3_3") (pintype "passive"))
      (node (ref "J5") (pin "3") (pinfunction "3_3") (pintype "passive"))
      (node (ref "R34") (pin "2") (pinfunction "2_2") (pintype "passive"))
      (node (ref "U1") (pin "8") (pinfunction "CRESET_B_8") (pintype "passive"))
      (node (ref "U10") (pin "7") (pinfunction "PA1_7") (pintype "passive"))
    )
    (net (code "41") (name "GND") (class "Default")
      (node (ref "C1") (pin "1") (pinfunction "1_1") (pintype "passive"))
      (node (ref "C10") (pin "1") (pinfunction "1_1") (pintype "passive"))
      (node (ref "C11") (pin "1") (pinfunction "1_1") (pintype "passive"))
      (node (ref "C12") (pin "1") (pinfunction "1_1") (pintype "passive"))
      (node (ref "C13") (pin "1") (pinfunction "1_1") (pintype "passive"))
      (node (ref "C14") (pin "1") (pinfunction "1_1") (pintype "passive"))
      (node (ref "C15") (pin "1") (pinfunction "1_1") (pintype "passive"))
      (node (ref "C16") (pin "1") (pinfunction "1_1") (pintype "passive"))
      (node (ref "C17") (pin "1") (pinfunction "1_1") (pintype "passive"))
      (node (ref "C18") (pin "1") (pinfunction "1_1") (pintype "passive"))
      (node (ref "C19") (pin "1") (pinfunction "1_1") (pintype "passive"))
      (node (ref "C2") (pin "1") (pinfunction "1_1") (pintype "passive"))
      (node (ref "C20") (pin "1") (pinfunction "1_1") (pintype "passive"))
      (node (ref "C21") (pin "1") (pinfunction "1_1") (pintype "passive"))
      (node (ref "C22") (pin "1") (pinfunction "1_1") (pintype "passive"))
      (node (ref "C23") (pin "1") (pinfunction "1_1") (pintype "passive"))
      (node (ref "C24") (pin "1") (pinfunction "1_1") (pintype "passive"))
      (node (ref "C25") (pin "1") (pinfunction "1_1") (pintype "passive"))
      (node (ref "C26") (pin "1") (pinfunction "1_1") (pintype "passive"))
      (node (ref "C27") (pin "1") (pinfunction "1_1") (pintype "passive"))
      (node (ref "C28") (pin "1") (pinfunction "1_1") (pintype "passive"))
      (node (ref "C29") (pin "1") (pinfunction "1_1") (pintype "passive"))
      (node (ref "C30") (pin "1") (pinfunction "1_1") (pintype "passive"))
      (node (ref "C4") (pin "1") (pinfunction "1_1") (pintype "passive"))
      (node (ref "C5") (pin "1") (pinfunction "1_1") (pintype "passive"))
      (node (ref "C6") (pin "1") (pinfunction "1_1") (pintype "passive"))
      (node (ref "C69") (pin "1") (pinfunction "1_1") (pintype "passive"))
      (node (ref "C7") (pin "1") (pinfunction "1_1") (pintype "passive"))
      (node (ref "C70") (pin "1") (pinfunction "1_1") (pintype "passive"))
      (node (ref "C8") (pin "1") (pinfunction "1_1") (pintype "passive"))
      (node (ref "C9") (pin "1") (pinfunction "1_1") (pintype "passive"))
      (node (ref "J1") (pin "11") (pinfunction "11_11") (pintype "passive"))
      (node (ref "J1") (pin "13") (pinfunction "13_13") (pintype "passive"))
      (node (ref "J1") (pin "15") (pinfunction "15_15") (pintype "passive"))
      (node (ref "J1") (pin "18") (pinfunction "18_18") (pintype "passive"))
      (node (ref "J1") (pin "2") (pinfunction "2_2") (pintype "passive"))
      (node (ref "J1") (pin "3") (pinfunction "3_3") (pintype "passive"))
      (node (ref "J1") (pin "4") (pinfunction "4_4") (pintype "passive"))
      (node (ref "J1") (pin "6") (pinfunction "6_6") (pintype "passive"))
      (node (ref "J1") (pin "8") (pinfunction "8_8") (pintype "passive"))
      (node (ref "J3") (pin "8") (pinfunction "8_8") (pintype "passive"))
      (node (ref "J4") (pin "9") (pinfunction "9_9") (pintype "passive"))
      (node (ref "J5") (pin "8") (pinfunction "8_8") (pintype "passive"))
      (node (ref "J7") (pin "5") (pinfunction "GND_5") (pintype "passive"))
      (node (ref "J8") (pin "3") (pinfunction "3_3") (pintype "passive"))
      (node (ref "J9") (pin "4") (pinfunction "4_4") (pintype "passive"))
      (node (ref "R2") (pin "1") (pinfunction "1_1") (pintype "passive"))
      (node (ref "R24") (pin "1") (pinfunction "1_1") (pintype "passive"))
      (node (ref "R28") (pin "2") (pinfunction "2_2") (pintype "passive"))
      (node (ref "R29") (pin "2") (pinfunction "2_2") (pintype "passive"))
      (node (ref "R38") (pin "1") (pinfunction "1_1") (pintype "passive"))
      (node (ref "R42") (pin "1") (pinfunction "1_1") (pintype "passive"))
      (node (ref "R45") (pin "1") (pinfunction "1_1") (pintype "passive"))
      (node (ref "U1") (pin "49") (pinfunction "GND_49") (pintype "passive"))
      (node (ref "U10") (pin "15") (pinfunction "VSS_15") (pintype "passive"))
      (node (ref "U11") (pin "2") (pinfunction "GND_2") (pintype "passive"))
      (node (ref "U2") (pin "5") (pinfunction "GND_5") (pintype "passive"))
      (node (ref "U3") (pin "11") (pinfunction "A10_11") (pintype "passive"))
      (node (ref "U3") (pin "12") (pinfunction "GND_12") (pintype "passive"))
      (node (ref "U3") (pin "23") (pinfunction "OE#_23") (pintype "passive"))
      (node (ref "U4") (pin "4") (pinfunction "VSS_4") (pintype "passive"))
      (node (ref "U5") (pin "2") (pinfunction "GND_2") (pintype "passive"))
      (node (ref "U6") (pin "11") (pinfunction "GND_11") (pintype "passive"))
      (node (ref "U6") (pin "12") (pinfunction "GND_12") (pintype "passive"))
      (node (ref "U6") (pin "13") (pinfunction "GND_13") (pintype "passive"))
      (node (ref "U7") (pin "2") (pinfunction "GND_2") (pintype "passive"))
      (node (ref "U8") (pin "2") (pinfunction "GND_2") (pintype "passive"))
      (node (ref "U9") (pin "3") (pinfunction "GND_3") (pintype "passive"))
    )
    (net (code "42") (name "NRST") (class "Default")
      (node (ref "J8") (pin "6") (pinfunction "6_6") (pintype "passive"))
      (node (ref "U10") (pin "4") (pinfunction "NRST_4") (pintype "passive"))
    )
    (net (code "43") (name "Net-(C3-Pad1)") (class "Default")
      (node (ref "C3") (pin "1") (pinfunction "1_1") (pintype "passive"))
      (node (ref "R33") (pin "2") (pinfunction "2_2") (pintype "passive"))
    )
    (net (code "44") (name "Net-(C16-Pad2)") (class "Default")
      (node (ref "C16") (pin "2") (pinfunction "2_2") (pintype "passive"))
      (node (ref "C17") (pin "2") (pinfunction "2_2") (pintype "passive"))
      (node (ref "R40") (pin "2") (pinfunction "2_2") (pintype "passive"))
      (node (ref "R41") (pin "1") (pinfunction "1_1") (pintype "passive"))
    )
    (net (code "45") (name "Net-(J7-D+)") (class "Default")
      (node (ref "J7") (pin "3") (pinfunction "D+_3") (pintype "passive"))
      (node (ref "U10") (pin "18") (pinfunction "PA10/PA12_18") (pintype "passive"))
    )
    (net (code "46") (name "Net-(J7-D-)") (class "Default")
      (node (ref "J7") (pin "2") (pinfunction "D-_2") (pintype "passive"))
      (node (ref "U10") (pin "17") (pinfunction "PA9/PA11_17") (pintype "passive"))
    )
    (net (code "47") (name "Net-(J7-PadMH1)") (class "Default")
      (node (ref "J7") (pin "MH1") (pinfunction "MH1_MH1") (pintype "passive"))
      (node (ref "J7") (pin "MH2") (pinfunction "MH2_MH2") (pintype "passive"))
      (node (ref "J7") (pin "MP1") (pinfunction "MP1_MP1") (pintype "passive"))
      (node (ref "J7") (pin "MP2") (pinfunction "MP2_MP2") (pintype "passive"))
      (node (ref "R38") (pin "2") (pinfunction "2_2") (pintype "passive"))
    )
    (net (code "48") (name "Net-(U1-VCCPLL)") (class "Default")
      (node (ref "R40") (pin "1") (pinfunction "1_1") (pintype "passive"))
      (node (ref "U1") (pin "29") (pinfunction "VCCPLL_29") (pintype "passive"))
    )
    (net (code "49") (name "Net-(U2-CH1_OUT)") (class "Default")
      (node (ref "R32") (pin "1") (pinfunction "1_1") (pintype "passive"))
      (node (ref "U2") (pin "8") (pinfunction "CH1_OUT_8") (pintype "passive"))
    )
    (net (code "50") (name "Net-(U2-CH2_OUT)") (class "Default")
      (node (ref "R31") (pin "1") (pinfunction "1_1") (pintype "passive"))
      (node (ref "R33") (pin "1") (pinfunction "1_1") (pintype "passive"))
      (node (ref "U2") (pin "7") (pinfunction "CH2_OUT_7") (pintype "passive"))
    )
    (net (code "51") (name "Net-(U2-CH3_OUT)") (class "Default")
      (node (ref "R30") (pin "1") (pinfunction "1_1") (pintype "passive"))
      (node (ref "U2") (pin "6") (pinfunction "CH3_OUT_6") (pintype "passive"))
    )
    (net (code "52") (name "Net-(U2-VCC)") (class "Default")
      (node (ref "C1") (pin "2") (pinfunction "2_2") (pintype "passive"))
      (node (ref "C2") (pin "2") (pinfunction "2_2") (pintype "passive"))
      (node (ref "R36") (pin "1") (pinfunction "1_1") (pintype "passive"))
      (node (ref "U2") (pin "4") (pinfunction "VCC_4") (pintype "passive"))
    )
    (net (code "53") (name "Net-(U4-DQ2{slash}WP#)") (class "Default")
      (node (ref "R43") (pin "2") (pinfunction "2_2") (pintype "passive"))
      (node (ref "U4") (pin "3") (pinfunction "DQ2/WP#_3") (pintype "passive"))
    )
    (net (code "54") (name "Net-(U4-DQ3{slash}HOLD#)") (class "Default")
      (node (ref "R44") (pin "2") (pinfunction "2_2") (pintype "passive"))
      (node (ref "U4") (pin "7") (pinfunction "DQ3/HOLD#_7") (pintype "passive"))
    )
    (net (code "55") (name "Net-(U6-DIR)") (class "Default")
      (node (ref "U6") (pin "2") (pinfunction "DIR_2") (pintype "passive"))
      (node (ref "U9") (pin "4") (pinfunction "Y_4") (pintype "passive"))
    )
    (net (code "56") (name "Net-(U7-FB)") (class "Default")
      (node (ref "R23") (pin "1") (pinfunction "1_1") (pintype "passive"))
      (node (ref "R24") (pin "2") (pinfunction "2_2") (pintype "passive"))
      (node (ref "U7") (pin "5") (pinfunction "FB_5") (pintype "passive"))
    )
    (net (code "57") (name "Net-(U7-LX)") (class "Default")
      (node (ref "L14") (pin "1") (pinfunction "1_1") (pintype "passive"))
      (node (ref "U7") (pin "3") (pinfunction "LX_3") (pintype "passive"))
    )
    (net (code "58") (name "Net-(U8-FB)") (class "Default")
      (node (ref "R13") (pin "1") (pinfunction "1_1") (pintype "passive"))
      (node (ref "R45") (pin "2") (pinfunction "2_2") (pintype "passive"))
      (node (ref "U8") (pin "5") (pinfunction "FB_5") (pintype "passive"))
    )
    (net (code "59") (name "Net-(U8-LX)") (class "Default")
      (node (ref "L1") (pin "1") (pinfunction "1_1") (pintype "passive"))
      (node (ref "U8") (pin "3") (pinfunction "LX_3") (pintype "passive"))
    )
    (net (code "60") (name "Net-(U10-PF0-OSC_IN)") (class "Default")
      (node (ref "C30") (pin "2") (pinfunction "2_2") (pintype "passive"))
      (node (ref "U10") (pin "2") (pinfunction "PF0-OSC_IN_2") (pintype "passive"))
      (node (ref "X2") (pin "2") (pinfunction "2_2") (pintype "passive"))
    )
    (net (code "61") (name "Net-(U10-PF1-OSC_OUT)") (class "Default")
      (node (ref "C29") (pin "2") (pinfunction "2_2") (pintype "passive"))
      (node (ref "U10") (pin "3") (pinfunction "PF1-OSC_OUT_3") (pintype "passive"))
      (node (ref "X2") (pin "1") (pinfunction "1_1") (pintype "passive"))
    )
    (net (code "62") (name "Net-(U10-VDD)") (class "Default")
      (node (ref "C20") (pin "2") (pinfunction "2_2") (pintype "passive"))
      (node (ref "C21") (pin "2") (pinfunction "2_2") (pintype "passive"))
      (node (ref "C22") (pin "2") (pinfunction "2_2") (pintype "passive"))
      (node (ref "C27") (pin "2") (pinfunction "2_2") (pintype "passive"))
      (node (ref "J2") (pin "1") (pinfunction "1_1") (pintype "passive"))
      (node (ref "J8") (pin "1") (pinfunction "1_1") (pintype "passive"))
      (node (ref "U10") (pin "16") (pinfunction "VDD_16") (pintype "passive"))
      (node (ref "U10") (pin "5") (pinfunction "VDDA_5") (pintype "passive"))
      (node (ref "U11") (pin "5") (pinfunction "VOUT_5") (pintype "passive"))
    )
    (net (code "63") (name "Net-(U11-BYP)") (class "Default")
      (node (ref "C24") (pin "2") (pinfunction "2_2") (pintype "passive"))
      (node (ref "U11") (pin "4") (pinfunction "BYP_4") (pintype "passive"))
    )
    (net (code "64") (name "SPI_MISO") (class "Default")
      (node (ref "J3") (pin "4") (pinfunction "4_4") (pintype "passive"))
      (node (ref "J5") (pin "4") (pinfunction "4_4") (pintype "passive"))
      (node (ref "U1") (pin "17") (pinfunction "IOB_33B_SPI_SI_17") (pintype "passive"))
      (node (ref "U10") (pin "12") (pinfunction "PA6_12") (pintype "passive"))
      (node (ref "U4") (pin "2") (pinfunction "DQ1_2") (pintype "passive"))
    )
    (net (code "65") (name "SPI_MOSI") (class "Default")
      (node (ref "J3") (pin "5") (pinfunction "5_5") (pintype "passive"))
      (node (ref "J5") (pin "5") (pinfunction "5_5") (pintype "passive"))
      (node (ref "U1") (pin "14") (pinfunction "IOB_32A_SPI_SO_14") (pintype "passive"))
      (node (ref "U10") (pin "13") (pinfunction "PA7_13") (pintype "passive"))
      (node (ref "U4") (pin "5") (pinfunction "DQ0_5") (pintype "passive"))
    )
    (net (code "66") (name "SPI_SCK") (class "Default")
      (node (ref "J3") (pin "6") (pinfunction "6_6") (pintype "passive"))
      (node (ref "J5") (pin "6") (pinfunction "6_6") (pintype "passive"))
      (node (ref "U1") (pin "15") (pinfunction "IOB_34A_SPI_SCK_15") (pintype "passive"))
      (node (ref "U10") (pin "11") (pinfunction "PA5_11") (pintype "passive"))
      (node (ref "U4") (pin "6") (pinfunction "CLK_6") (pintype "passive"))
    )
    (net (code "67") (name "SPI_SSEL_N") (class "Default")
      (node (ref "J3") (pin "7") (pinfunction "7_7") (pintype "passive"))
      (node (ref "J5") (pin "7") (pinfunction "7_7") (pintype "passive"))
      (node (ref "R46") (pin "2") (pinfunction "2_2") (pintype "passive"))
      (node (ref "U1") (pin "16") (pinfunction "IOB_35B_SPI_SS_16") (pintype "passive"))
      (node (ref "U10") (pin "10") (pinfunction "PA4_10") (pintype "passive"))
      (node (ref "U4") (pin "1") (pinfunction "CS#_1") (pintype "passive"))
    )
    (net (code "68") (name "SWCLK") (class "Default")
      (node (ref "J8") (pin "2") (pinfunction "2_2") (pintype "passive"))
      (node (ref "U10") (pin "20") (pinfunction "PA14/SWCLK_20") (pintype "passive"))
    )
    (net (code "69") (name "SWDIO") (class "Default")
      (node (ref "J8") (pin "4") (pinfunction "4_4") (pintype "passive"))
      (node (ref "U10") (pin "19") (pinfunction "PA13/SWDIO_19") (pintype "passive"))
    )
    (net (code "70") (name "SYSCLK") (class "Default")
      (node (ref "U1") (pin "35") (pinfunction "IOT_46B_G0_35") (pintype "passive"))
      (node (ref "U5") (pin "3") (pinfunction "OUT_3") (pintype "passive"))
    )
    (net (code "71") (name "UART_RXD") (class "Default")
      (node (ref "J9") (pin "3") (pinfunction "3_3") (pintype "passive"))
      (node (ref "U10") (pin "9") (pinfunction "PA3_9") (pintype "passive"))
    )
    (net (code "72") (name "UART_TXD") (class "Default")
      (node (ref "J9") (pin "2") (pinfunction "2_2") (pintype "passive"))
      (node (ref "U10") (pin "8") (pinfunction "PA2_8") (pintype "passive"))
    )
    (net (code "73") (name "VBUS") (class "Default")
      (node (ref "C28") (pin "2") (pinfunction "2_2") (pintype "passive"))
      (node (ref "J6") (pin "2") (pinfunction "2_2") (pintype "passive"))
      (node (ref "J7") (pin "1") (pinfunction "VBUS_1") (pintype "passive"))
      (node (ref "U11") (pin "1") (pinfunction "VIN_1") (pintype "passive"))
      (node (ref "U11") (pin "3") (pinfunction "SHDN#_3") (pintype "passive"))
    )
    (net (code "74") (name "VGA_B") (class "Default")
      (node (ref "J1") (pin "14") (pinfunction "14_14") (pintype "passive"))
      (node (ref "R19") (pin "2") (pinfunction "2_2") (pintype "passive"))
      (node (ref "R20") (pin "2") (pinfunction "2_2") (pintype "passive"))
      (node (ref "R21") (pin "2") (pinfunction "2_2") (pintype "passive"))
      (node (ref "R22") (pin "2") (pinfunction "2_2") (pintype "passive"))
    )
    (net (code "75") (name "VGA_B0") (class "Default")
      (node (ref "R22") (pin "1") (pinfunction "1_1") (pintype "passive"))
      (node (ref "U1") (pin "46") (pinfunction "IOB_0A_46") (pintype "passive"))
    )
    (net (code "76") (name "VGA_B1") (class "Default")
      (node (ref "R21") (pin "1") (pinfunction "1_1") (pintype "passive"))
      (node (ref "U1") (pin "47") (pinfunction "IOB_2A_47") (pintype "passive"))
    )
    (net (code "77") (name "VGA_B2") (class "Default")
      (node (ref "R20") (pin "1") (pinfunction "1_1") (pintype "passive"))
      (node (ref "U1") (pin "48") (pinfunction "IOB_4A_48") (pintype "passive"))
    )
    (net (code "78") (name "VGA_B3") (class "Default")
      (node (ref "R19") (pin "1") (pinfunction "1_1") (pintype "passive"))
      (node (ref "U1") (pin "2") (pinfunction "IOB_6A_2") (pintype "passive"))
    )
    (net (code "79") (name "VGA_G") (class "Default")
      (node (ref "J1") (pin "12") (pinfunction "12_12") (pintype "passive"))
      (node (ref "R11") (pin "2") (pinfunction "2_2") (pintype "passive"))
      (node (ref "R12") (pin "2") (pinfunction "2_2") (pintype "passive"))
      (node (ref "R17") (pin "2") (pinfunction "2_2") (pintype "passive"))
      (node (ref "R18") (pin "2") (pinfunction "2_2") (pintype "passive"))
    )
    (net (code "80") (name "VGA_G0") (class "Default")
      (node (ref "R18") (pin "1") (pinfunction "1_1") (pintype "passive"))
      (node (ref "R27") (pin "1") (pinfunction "1_1") (pintype "passive"))
      (node (ref "U1") (pin "3") (pinfunction "IOB_9B_3") (pintype "passive"))
    )
    (net (code "81") (name "VGA_G1") (class "Default")
      (node (ref "R17") (pin "1") (pinfunction "1_1") (pintype "passive"))
      (node (ref "R26") (pin "1") (pinfunction "1_1") (pintype "passive"))
      (node (ref "U1") (pin "4") (pinfunction "IOB_8A_4") (pintype "passive"))
    )
    (net (code "82") (name "VGA_G2") (class "Default")
      (node (ref "R12") (pin "1") (pinfunction "1_1") (pintype "passive"))
      (node (ref "R25") (pin "1") (pinfunction "1_1") (pintype "passive"))
      (node (ref "U1") (pin "6") (pinfunction "IOB_13B_6") (pintype "passive"))
    )
    (net (code "83") (name "VGA_G3") (class "Default")
      (node (ref "R11") (pin "1") (pinfunction "1_1") (pintype "passive"))
      (node (ref "R16") (pin "1") (pinfunction "1_1") (pintype "passive"))
      (node (ref "U1") (pin "9") (pinfunction "IOB_16A_9") (pintype "passive"))
    )
    (net (code "84") (name "VGA_HS") (class "Default")
      (node (ref "J1") (pin "17") (pinfunction "17_17") (pintype "passive"))
      (node (ref "R5") (pin "2") (pinfunction "2_2") (pintype "passive"))
    )
    (net (code "85") (name "VGA_HSYNC") (class "Default")
      (node (ref "R1") (pin "1") (pinfunction "1_1") (pintype "passive"))
      (node (ref "R5") (pin "1") (pinfunction "1_1") (pintype "passive"))
      (node (ref "U1") (pin "44") (pinfunction "IOB_3B_G6_44") (pintype "passive"))
    )
    (net (code "86") (name "VGA_R") (class "Default")
      (node (ref "J1") (pin "10") (pinfunction "10_10") (pintype "passive"))
      (node (ref "R10") (pin "2") (pinfunction "2_2") (pintype "passive"))
      (node (ref "R4") (pin "2") (pinfunction "2_2") (pintype "passive"))
      (node (ref "R8") (pin "2") (pinfunction "2_2") (pintype "passive"))
      (node (ref "R9") (pin "2") (pinfunction "2_2") (pintype "passive"))
    )
    (net (code "87") (name "VGA_R0") (class "Default")
      (node (ref "R10") (pin "1") (pinfunction "1_1") (pintype "passive"))
      (node (ref "R15") (pin "1") (pinfunction "1_1") (pintype "passive"))
      (node (ref "U1") (pin "10") (pinfunction "IOB_18A_10") (pintype "passive"))
    )
    (net (code "88") (name "VGA_R1") (class "Default")
      (node (ref "R14") (pin "1") (pinfunction "1_1") (pintype "passive"))
      (node (ref "R9") (pin "1") (pinfunction "1_1") (pintype "passive"))
      (node (ref "U1") (pin "11") (pinfunction "IOB_20A_11") (pintype "passive"))
    )
    (net (code "89") (name "VGA_R2") (class "Default")
      (node (ref "R7") (pin "1") (pinfunction "1_1") (pintype "passive"))
      (node (ref "R8") (pin "1") (pinfunction "1_1") (pintype "passive"))
      (node (ref "U1") (pin "12") (pinfunction "IOB_22A_12") (pintype "passive"))
    )
    (net (code "90") (name "VGA_R3") (class "Default")
      (node (ref "R3") (pin "1") (pinfunction "1_1") (pintype "passive"))
      (node (ref "R4") (pin "1") (pinfunction "1_1") (pintype "passive"))
      (node (ref "U1") (pin "13") (pinfunction "IOB_24A_13") (pintype "passive"))
    )
    (net (code "91") (name "VGA_VS") (class "Default")
      (node (ref "J1") (pin "16") (pinfunction "16_16") (pintype "passive"))
      (node (ref "R6") (pin "2") (pinfunction "2_2") (pintype "passive"))
    )
    (net (code "92") (name "VGA_VSYNC") (class "Default")
      (node (ref "R6") (pin "1") (pinfunction "1_1") (pintype "passive"))
      (node (ref "U1") (pin "45") (pinfunction "IOB_5B_45") (pintype "passive"))
    )
    (net (code "93") (name "VIDEO_C") (class "Default")
      (node (ref "J1") (pin "7") (pinfunction "7_7") (pintype "passive"))
      (node (ref "R31") (pin "2") (pinfunction "2_2") (pintype "passive"))
    )
    (net (code "94") (name "VIDEO_CHROMA") (class "Default")
      (node (ref "R14") (pin "2") (pinfunction "2_2") (pintype "passive"))
      (node (ref "R15") (pin "2") (pinfunction "2_2") (pintype "passive"))
      (node (ref "R2") (pin "2") (pinfunction "2_2") (pintype "passive"))
      (node (ref "R28") (pin "1") (pinfunction "1_1") (pintype "passive"))
      (node (ref "R3") (pin "2") (pinfunction "2_2") (pintype "passive"))
      (node (ref "R7") (pin "2") (pinfunction "2_2") (pintype "passive"))
      (node (ref "U2") (pin "2") (pinfunction "CH2_IN_2") (pintype "passive"))
    )
    (net (code "95") (name "VIDEO_COMP") (class "Default")
      (node (ref "C3") (pin "2") (pinfunction "2_2") (pintype "passive"))
      (node (ref "J1") (pin "5") (pinfunction "5_5") (pintype "passive"))
      (node (ref "R32") (pin "2") (pinfunction "2_2") (pintype "passive"))
    )
    (net (code "96") (name "VIDEO_LUMA") (class "Default")
      (node (ref "R1") (pin "2") (pinfunction "2_2") (pintype "passive"))
      (node (ref "R16") (pin "2") (pinfunction "2_2") (pintype "passive"))
      (node (ref "R25") (pin "2") (pinfunction "2_2") (pintype "passive"))
      (node (ref "R26") (pin "2") (pinfunction "2_2") (pintype "passive"))
      (node (ref "R27") (pin "2") (pinfunction "2_2") (pintype "passive"))
      (node (ref "R29") (pin "1") (pinfunction "1_1") (pintype "passive"))
      (node (ref "U2") (pin "1") (pinfunction "CH1_IN_1") (pintype "passive"))
      (node (ref "U2") (pin "3") (pinfunction "CH3_IN_3") (pintype "passive"))
    )
    (net (code "97") (name "VIDEO_Y") (class "Default")
      (node (ref "J1") (pin "9") (pinfunction "9_9") (pintype "passive"))
      (node (ref "R30") (pin "2") (pinfunction "2_2") (pintype "passive"))
    )
    (net (code "98") (name "unconnected-(J7-ID-Pad4)") (class "Default")
      (node (ref "J7") (pin "4") (pinfunction "ID_4") (pintype "passive"))
    )
    (net (code "99") (name "unconnected-(J8-Pad5)") (class "Default")
      (node (ref "J8") (pin "5") (pinfunction "5_5") (pintype "passive"))
    )
    (net (code "100") (name "unconnected-(J9-Pad1)") (class "Default")
      (node (ref "J9") (pin "1") (pinfunction "1_1") (pintype "passive"))
    )
    (net (code "101") (name "unconnected-(U1-RGB0-Pad39)") (class "Default")
      (node (ref "U1") (pin "39") (pinfunction "RGB0_39") (pintype "passive"))
    )
    (net (code "102") (name "unconnected-(U1-RGB1-Pad40)") (class "Default")
      (node (ref "U1") (pin "40") (pinfunction "RGB1_40") (pintype "passive"))
    )
    (net (code "103") (name "unconnected-(U1-RGB2-Pad41)") (class "Default")
      (node (ref "U1") (pin "41") (pinfunction "RGB2_41") (pintype "passive"))
    )
    (net (code "104") (name "unconnected-(U3-B10-Pad13)") (class "Default")
      (node (ref "U3") (pin "13") (pinfunction "B10_13") (pintype "passive"))
    )
    (net (code "105") (name "unconnected-(U5-OE-Pad1)") (class "Default")
      (node (ref "U5") (pin "1") (pinfunction "OE_1") (pintype "passive"))
    )
    (net (code "106") (name "unconnected-(U10-PB1-Pad14)") (class "Default")
      (node (ref "U10") (pin "14") (pinfunction "PB1_14") (pintype "passive"))
    )
  )
)
